# DroneMainBoard.net
KiCad netlist of a schematic drawn in EAGLE
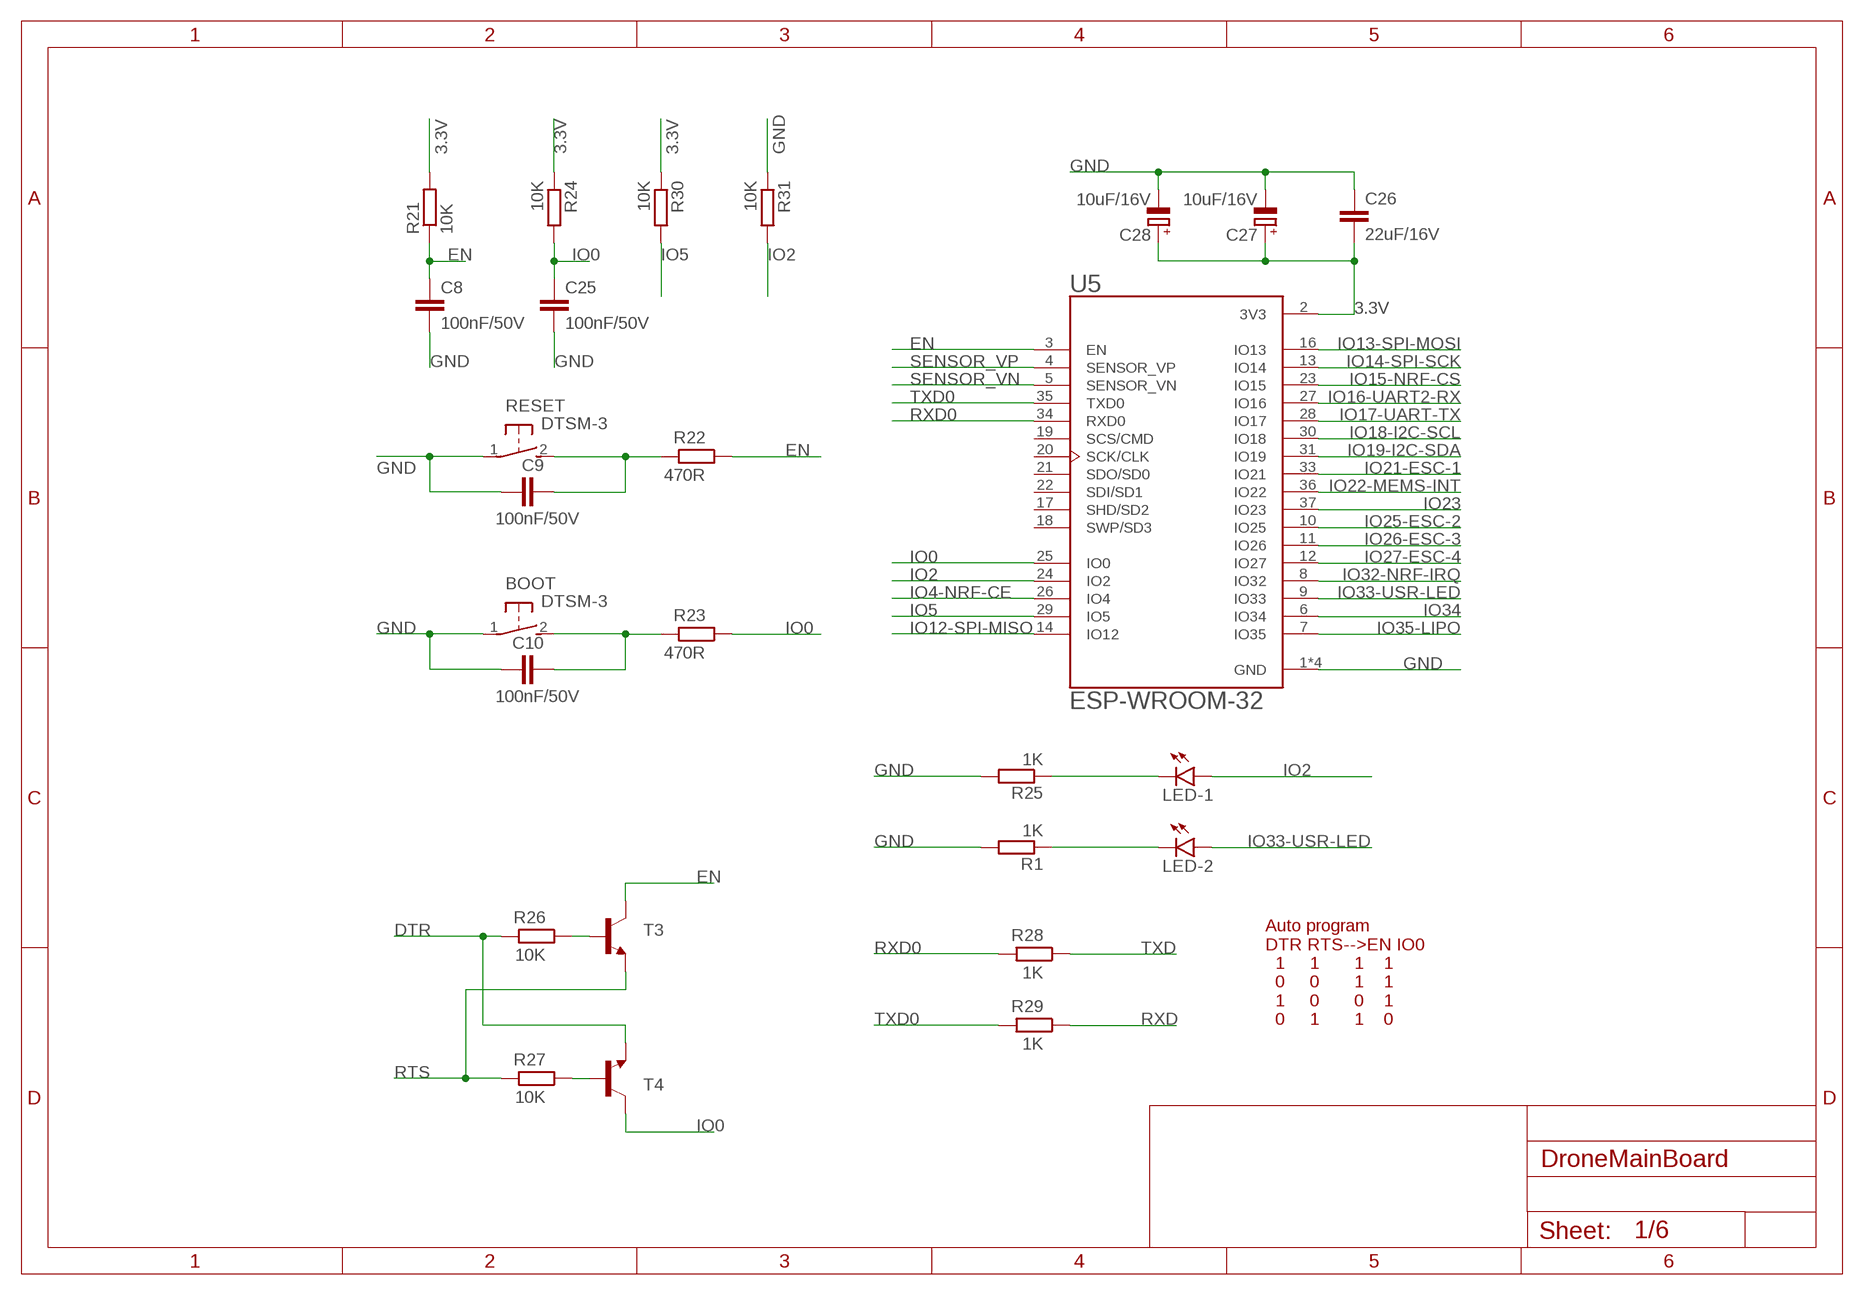
[diagram p0: schematic, sheet 1]
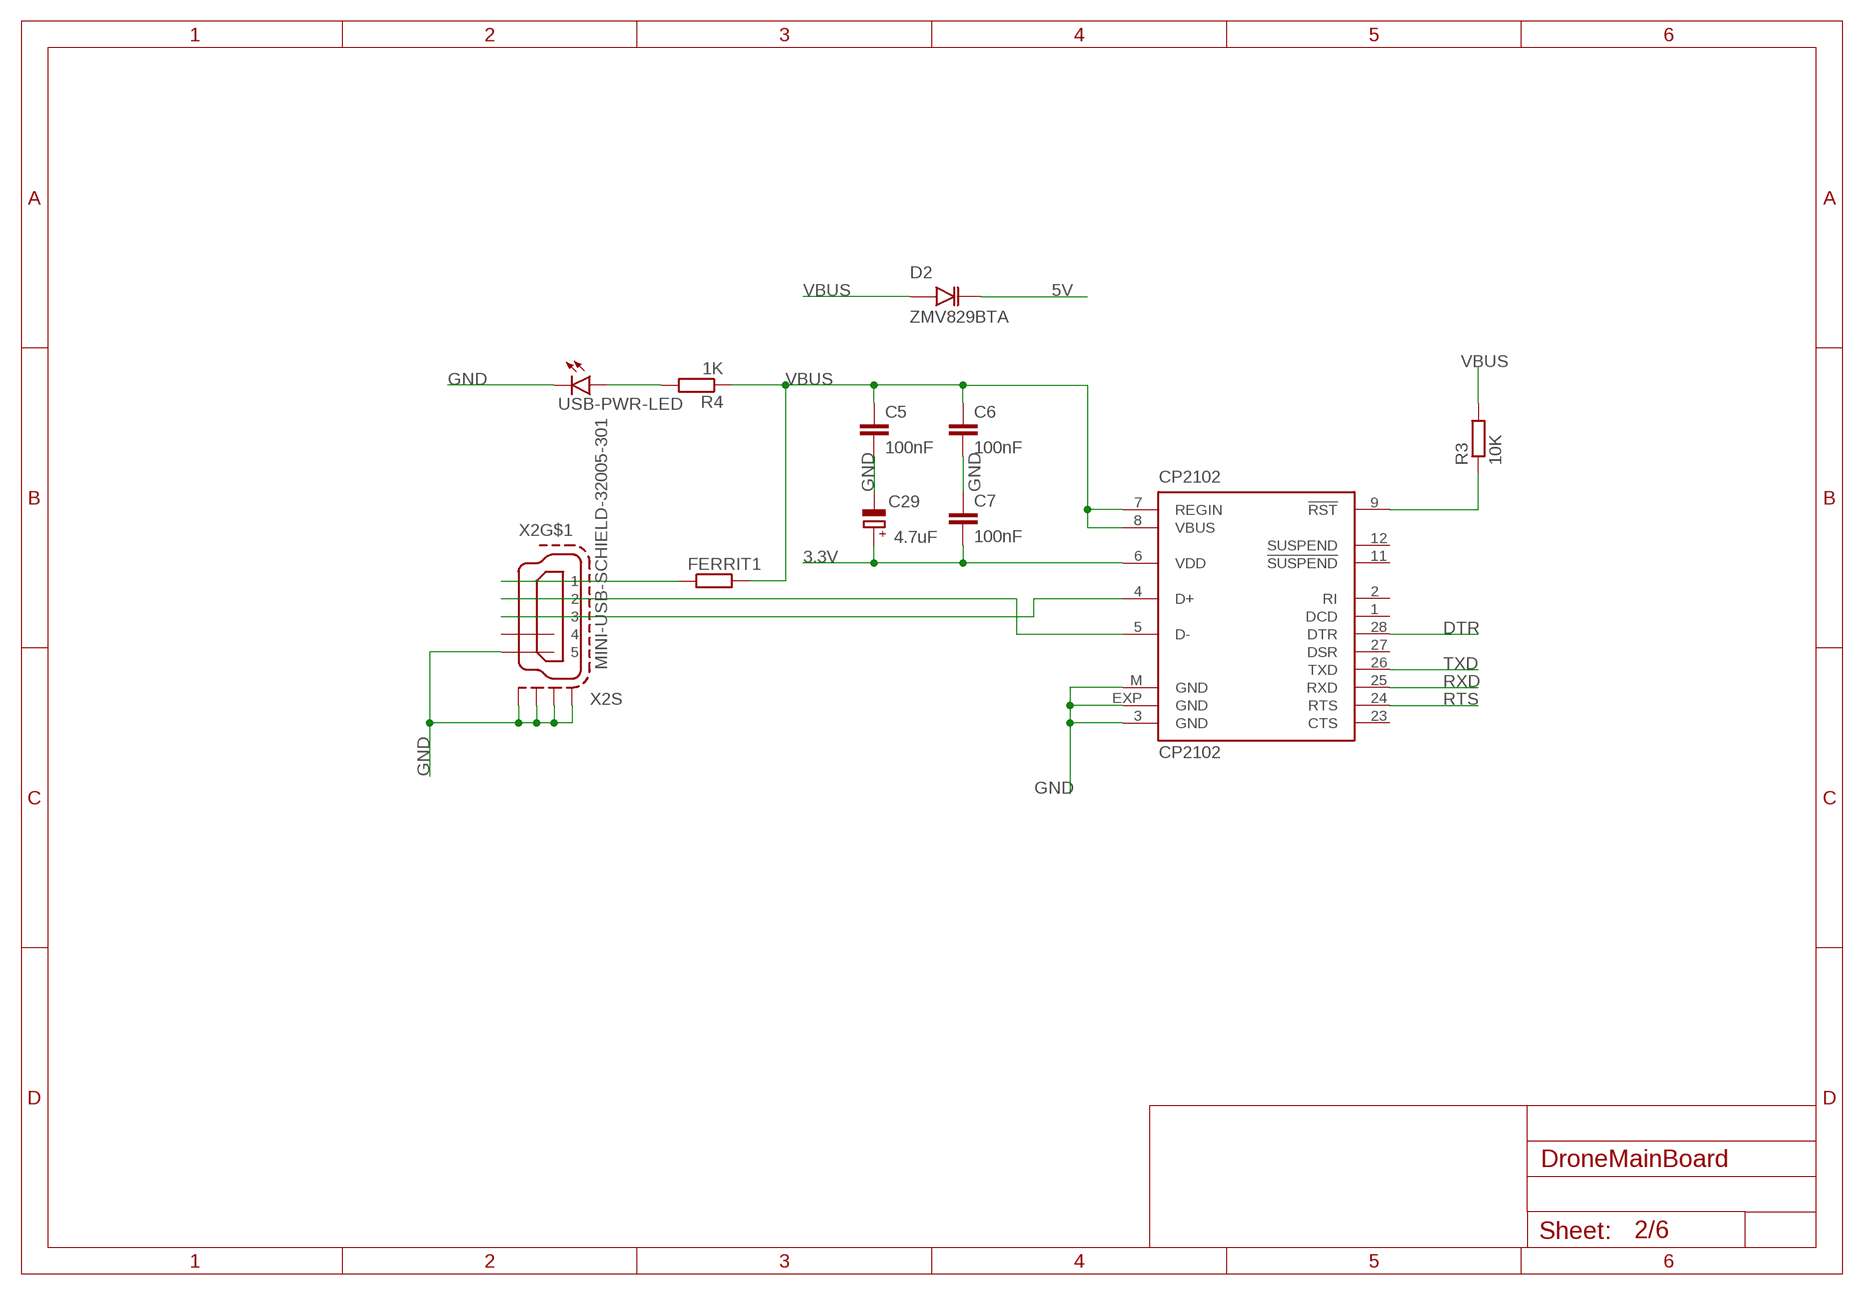
[diagram p1: schematic, sheet 2]
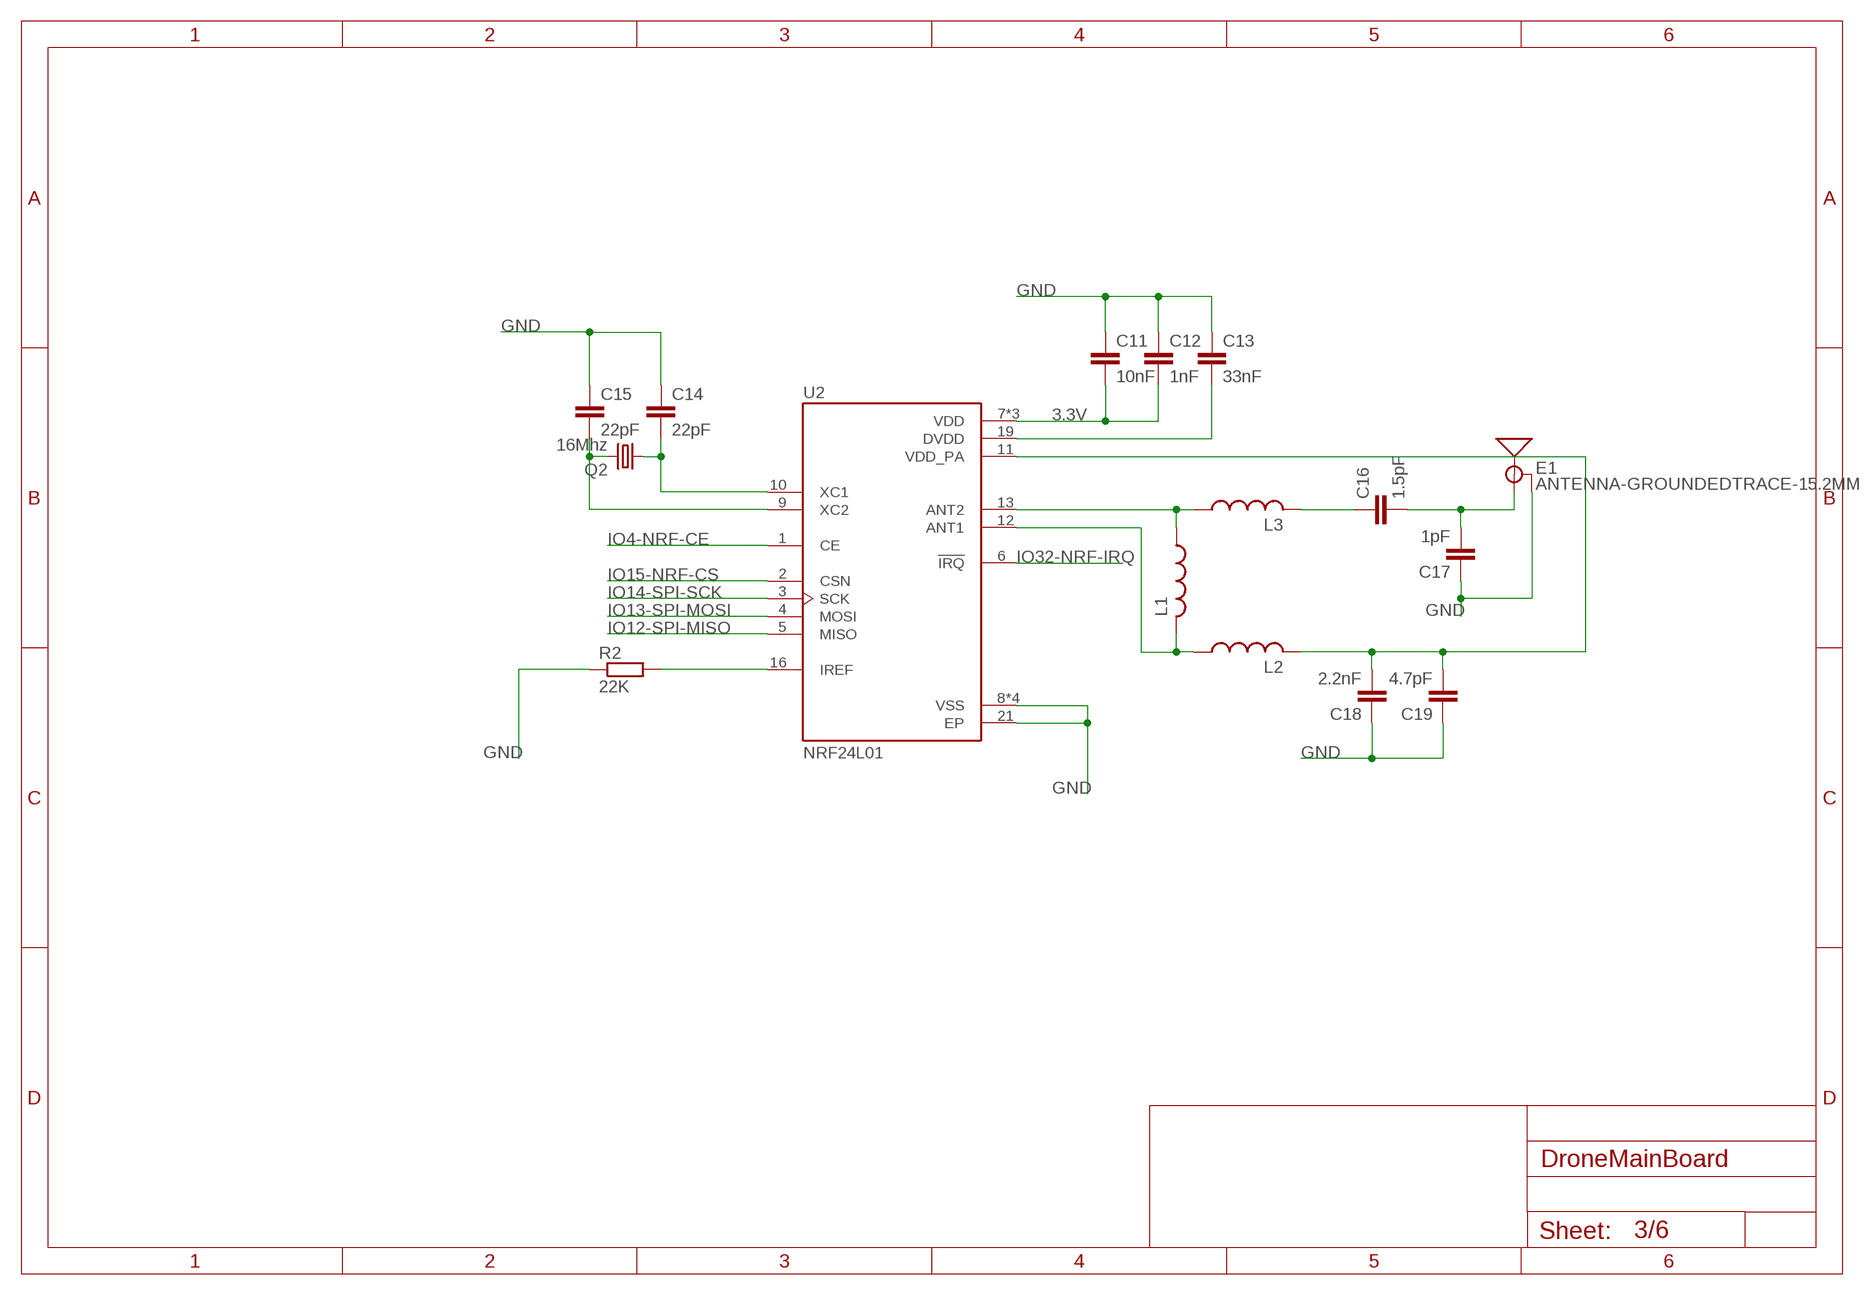
[diagram p2: schematic, sheet 3]
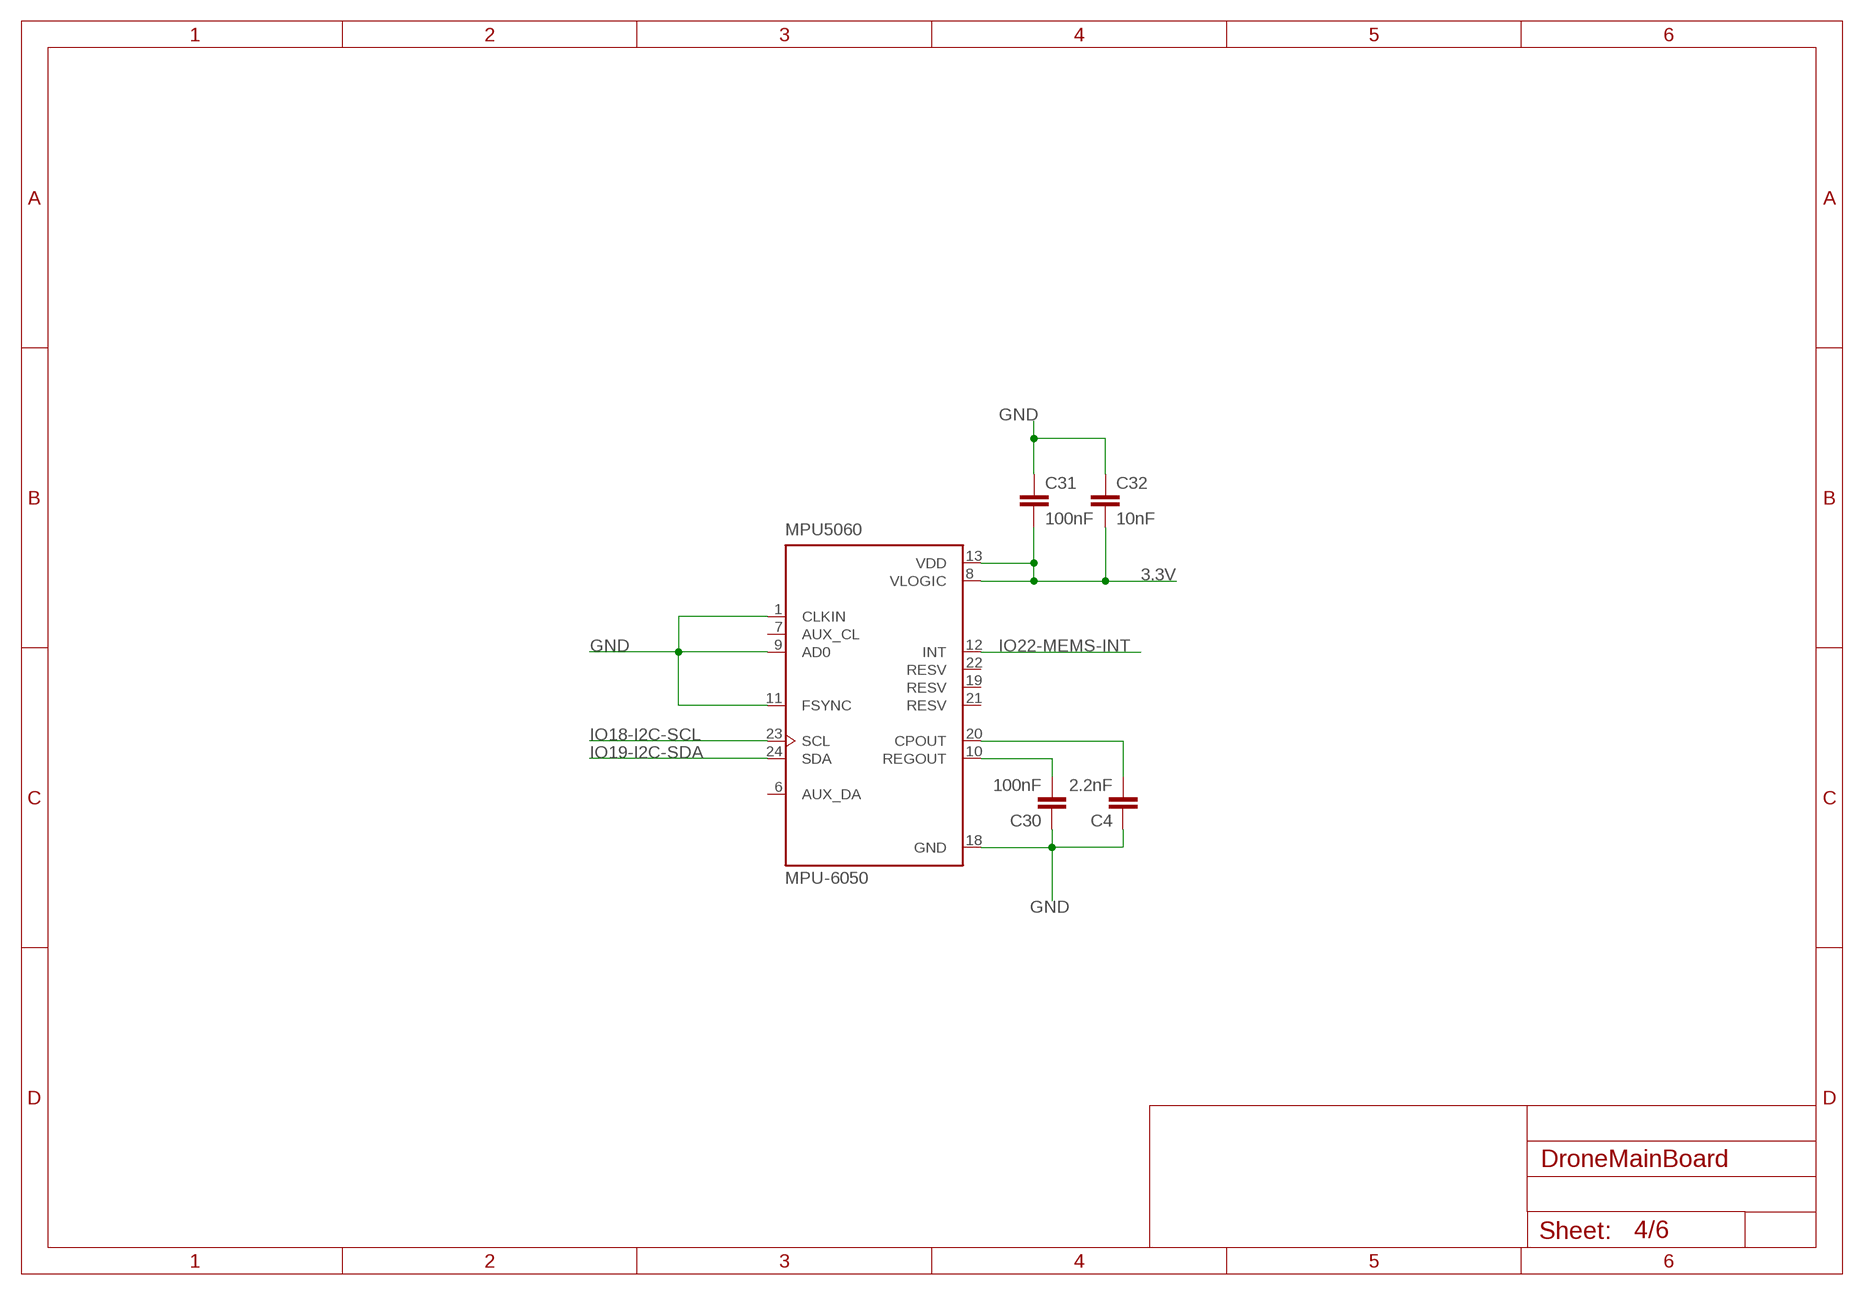
[diagram p3: schematic, sheet 4]
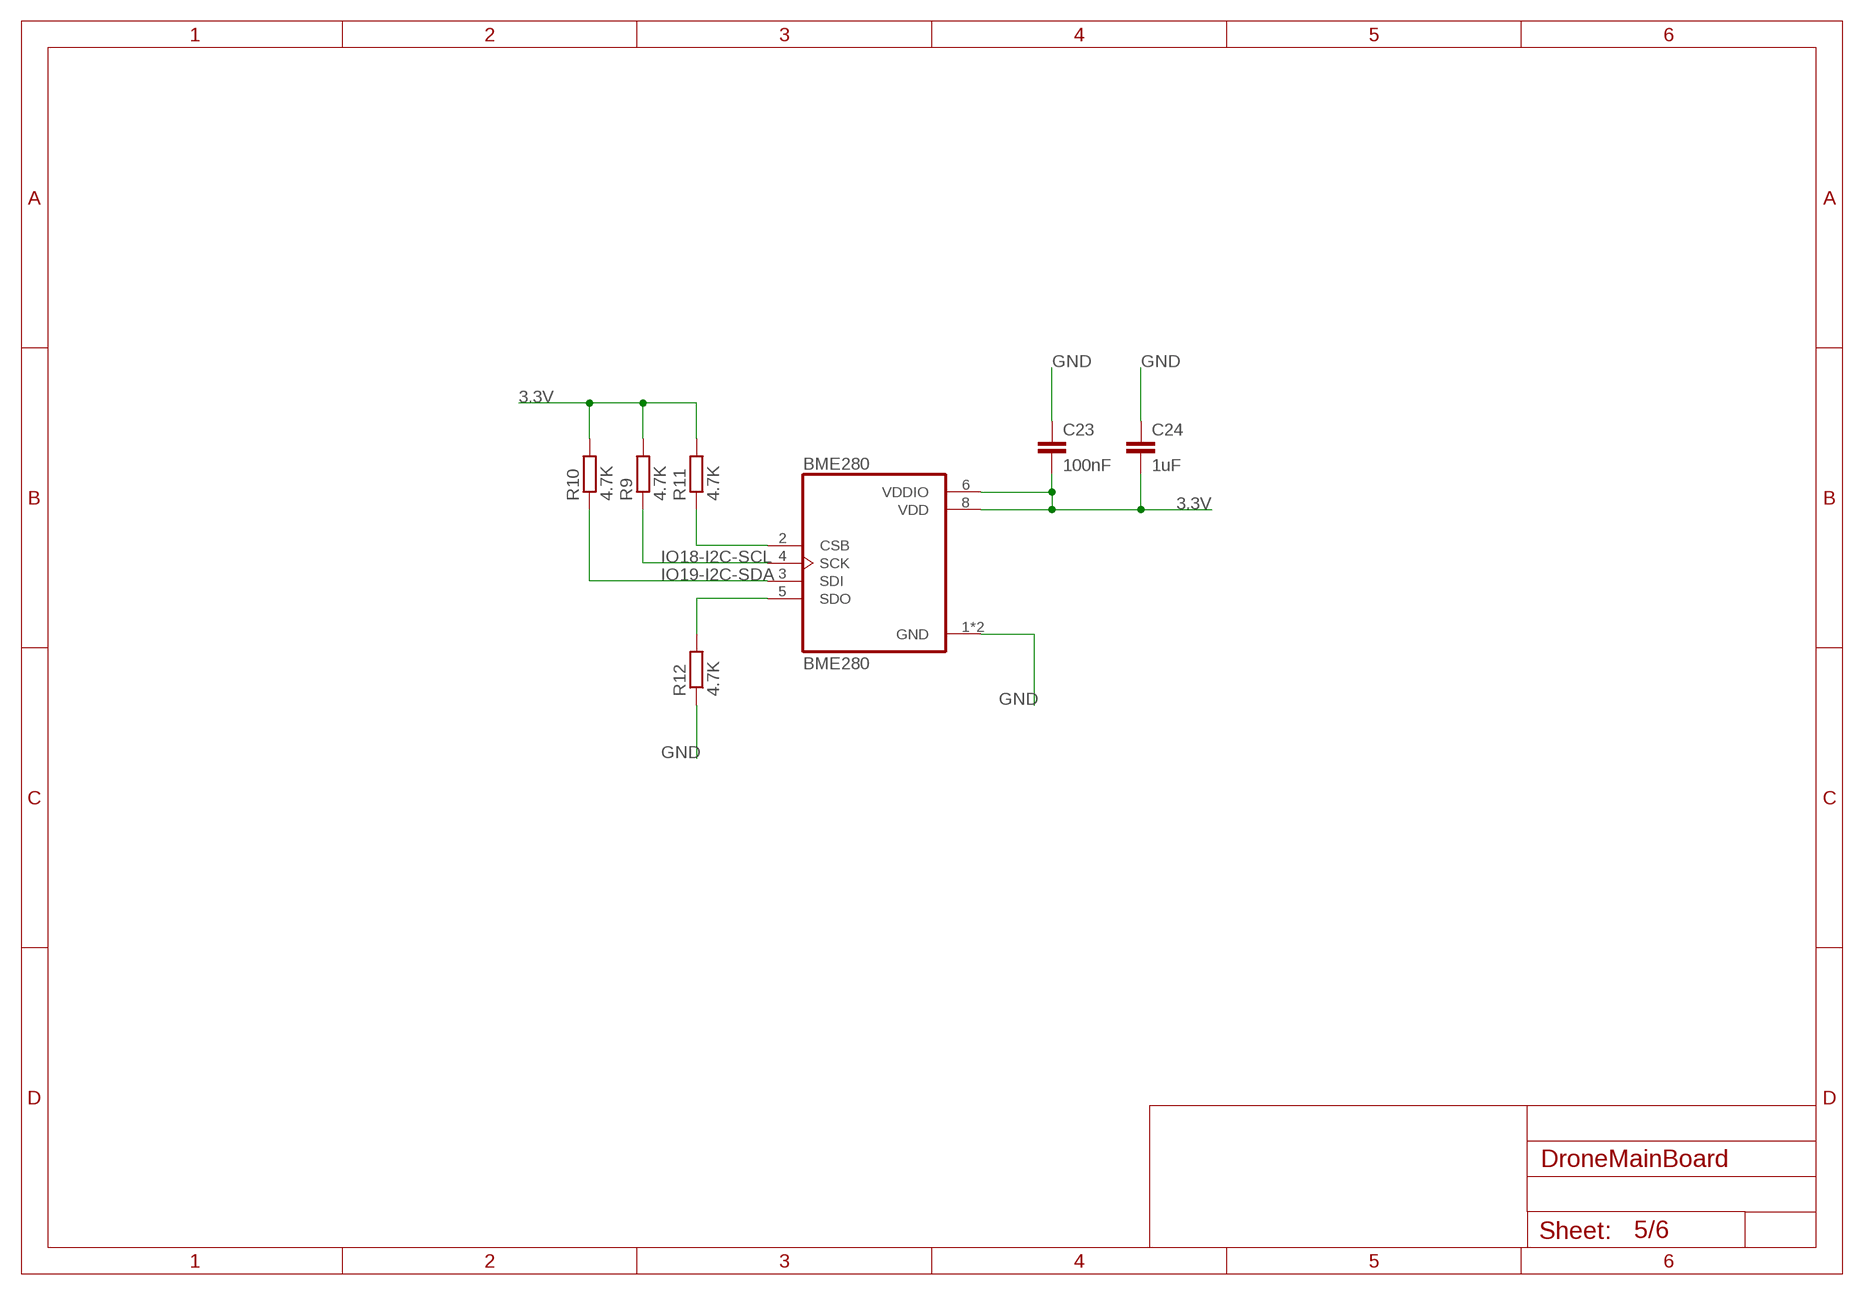
[diagram p4: schematic, sheet 5]
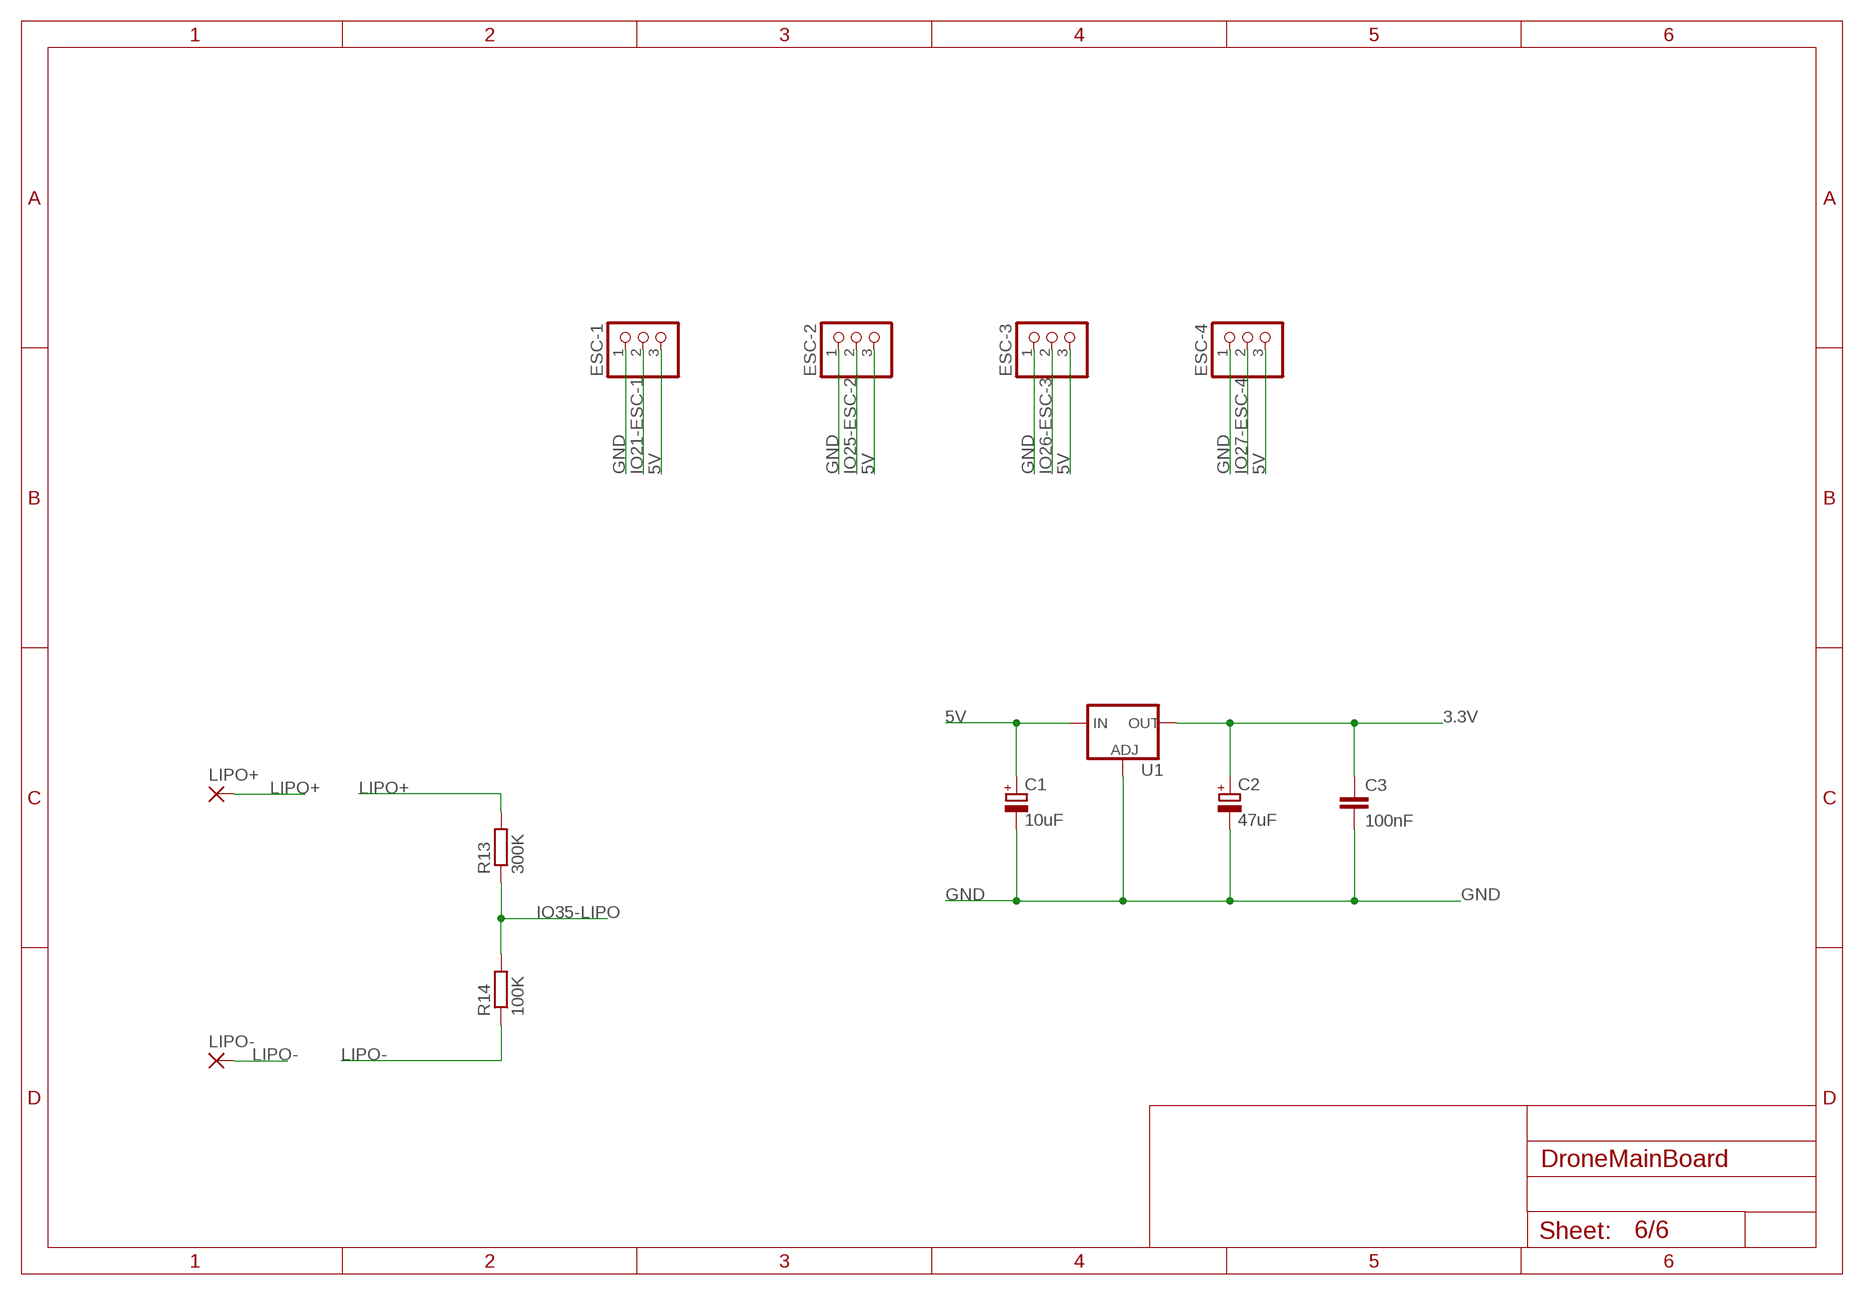
[diagram p5: schematic, sheet 6]

(export (version "E")
  (design (tool "Eeschema 10.0.6"))
  (components
    (comp (ref "C4")
      (value "2.2nF")
      (footprint "eagle-import:C0805")
      (libsource (lib "eagle-import") (part "C-EUC0805"))
    )
    (comp (ref "C30")
      (value "100nF")
      (footprint "eagle-import:C0805")
      (libsource (lib "eagle-import") (part "C-EUC0805"))
    )
    (comp (ref "C31")
      (value "100nF")
      (footprint "eagle-import:C0805")
      (libsource (lib "eagle-import") (part "C-EUC0805"))
    )
    (comp (ref "C32")
      (value "10nF")
      (footprint "eagle-import:C0805")
      (libsource (lib "eagle-import") (part "C-EUC0805"))
    )
    (comp (ref "MPU5060")
      (value "MPU-6050")
      (footprint "eagle-import:QFN50P400X400X95-24N")
      (fields (field (name "MF") "TDK InvenSense"))
      (libsource (lib "eagle-import") (part "MPU-6050"))
    )
    (comp (ref "C5")
      (value "100nF")
      (footprint "eagle-import:C0805")
      (libsource (lib "eagle-import") (part "C-EUC0805"))
    )
    (comp (ref "C6")
      (value "100nF")
      (footprint "eagle-import:C0805")
      (libsource (lib "eagle-import") (part "C-EUC0805"))
    )
    (comp (ref "C7")
      (value "100nF")
      (footprint "eagle-import:C0805")
      (libsource (lib "eagle-import") (part "C-EUC0805"))
    )
    (comp (ref "C29")
      (value "4.7uF")
      (footprint "eagle-import:SMC_A")
      (libsource (lib "eagle-import") (part "CPOL-EUSMCA"))
    )
    (comp (ref "CP2102")
      (value "CP2102")
      (footprint "eagle-import:MLP28")
      (fields (field (name "MF") "FARNELL") (field (name "MPN") "CP2102-GM"))
      (libsource (lib "eagle-import") (part "CP2102"))
    )
    (comp (ref "D2")
      (value "ZMV829BTA")
      (footprint "eagle-import:SOD2512X116N")
      (fields (field (name "MF") "Diodes Inc."))
      (libsource (lib "eagle-import") (part "ZMV829BTA"))
    )
    (comp (ref "FERRIT1")
      (value "R-EU_R0805")
      (footprint "eagle-import:R0805")
      (libsource (lib "eagle-import") (part "R-EU_R0805"))
    )
    (comp (ref "R3")
      (value "10K")
      (footprint "eagle-import:R0805")
      (libsource (lib "eagle-import") (part "R-EU_R0805"))
    )
    (comp (ref "R4")
      (value "1K")
      (footprint "eagle-import:R0805")
      (libsource (lib "eagle-import") (part "R-EU_R0805"))
    )
    (comp (ref "USB-PWR-LED")
      (value "LEDCHIPLED_0805")
      (footprint "eagle-import:CHIPLED_0805")
      (libsource (lib "eagle-import") (part "LEDCHIPLED_0805"))
    )
    (comp (ref "X2")
      (value "MINI-USB-SCHIELD-32005-301")
      (footprint "eagle-import:32005-301")
      (libsource (lib "eagle-import") (part "MINI-USB-SCHIELD-32005-301"))
    )
    (comp (ref "C1")
      (value "10uF")
      (footprint "eagle-import:SMC_A")
      (libsource (lib "eagle-import") (part "CPOL-EUSMCA"))
    )
    (comp (ref "C2")
      (value "47uF")
      (footprint "eagle-import:SMC_A")
      (libsource (lib "eagle-import") (part "CPOL-EUSMCA"))
    )
    (comp (ref "C3")
      (value "100nF")
      (footprint "eagle-import:C0805")
      (libsource (lib "eagle-import") (part "C-EUC0805"))
    )
    (comp (ref "ESC-1")
      (value "PINHD-1X3")
      (footprint "eagle-import:1X03")
      (libsource (lib "eagle-import") (part "PINHD-1X3"))
    )
    (comp (ref "ESC-2")
      (value "PINHD-1X3")
      (footprint "eagle-import:1X03")
      (libsource (lib "eagle-import") (part "PINHD-1X3"))
    )
    (comp (ref "ESC-3")
      (value "PINHD-1X3")
      (footprint "eagle-import:1X03")
      (libsource (lib "eagle-import") (part "PINHD-1X3"))
    )
    (comp (ref "ESC-4")
      (value "PINHD-1X3")
      (footprint "eagle-import:1X03")
      (libsource (lib "eagle-import") (part "PINHD-1X3"))
    )
    (comp (ref "LIPO+")
      (value "2,15/1,0")
      (footprint "eagle-import:2,15_1,0")
      (libsource (lib "eagle-import") (part "2,15/1,0"))
    )
    (comp (ref "LIPO-")
      (value "2,15/1,0")
      (footprint "eagle-import:2,15_1,0")
      (libsource (lib "eagle-import") (part "2,15/1,0"))
    )
    (comp (ref "R13")
      (value "300K")
      (footprint "eagle-import:R0805")
      (libsource (lib "eagle-import") (part "R-EU_R0805"))
    )
    (comp (ref "R14")
      (value "100K")
      (footprint "eagle-import:R0805")
      (libsource (lib "eagle-import") (part "R-EU_R0805"))
    )
    (comp (ref "U1")
      (value "V_REG_LM1117SOT223")
      (footprint "eagle-import:SOT223")
      (libsource (lib "eagle-import") (part "V_REG_LM1117SOT223"))
    )
    (comp (ref "BOOT")
      (value "DTSM-3")
      (footprint "eagle-import:DTSM-3")
      (libsource (lib "eagle-import") (part "DTSM-3"))
    )
    (comp (ref "C8")
      (value "100nF/50V")
      (footprint "eagle-import:C0805")
      (libsource (lib "eagle-import") (part "C-EUC0805"))
    )
    (comp (ref "C9")
      (value "100nF/50V")
      (footprint "eagle-import:C0805")
      (libsource (lib "eagle-import") (part "C-EUC0805"))
    )
    (comp (ref "C10")
      (value "100nF/50V")
      (footprint "eagle-import:C0805")
      (libsource (lib "eagle-import") (part "C-EUC0805"))
    )
    (comp (ref "C25")
      (value "100nF/50V")
      (footprint "eagle-import:C0805")
      (libsource (lib "eagle-import") (part "C-EUC0805"))
    )
    (comp (ref "C26")
      (value "22uF/16V")
      (footprint "eagle-import:C0805")
      (libsource (lib "eagle-import") (part "C-EUC0805"))
    )
    (comp (ref "C27")
      (value "10uF/16V")
      (footprint "eagle-import:SMC_A")
      (libsource (lib "eagle-import") (part "CPOL-EUSMCA"))
    )
    (comp (ref "C28")
      (value "10uF/16V")
      (footprint "eagle-import:SMC_A")
      (libsource (lib "eagle-import") (part "CPOL-EUSMCA"))
    )
    (comp (ref "LED-1")
      (value "LEDCHIP-LED0805")
      (footprint "eagle-import:CHIP-LED0805")
      (libsource (lib "eagle-import") (part "LEDCHIP-LED0805"))
    )
    (comp (ref "LED-2")
      (value "LEDCHIP-LED0805")
      (footprint "eagle-import:CHIP-LED0805")
      (libsource (lib "eagle-import") (part "LEDCHIP-LED0805"))
    )
    (comp (ref "R1")
      (value "1K")
      (footprint "eagle-import:R0805")
      (libsource (lib "eagle-import") (part "R-EU_R0805"))
    )
    (comp (ref "R21")
      (value "10K")
      (footprint "eagle-import:R0805")
      (libsource (lib "eagle-import") (part "R-EU_R0805"))
    )
    (comp (ref "R22")
      (value "470R")
      (footprint "eagle-import:R0805")
      (libsource (lib "eagle-import") (part "R-EU_R0805"))
    )
    (comp (ref "R23")
      (value "470R")
      (footprint "eagle-import:R0805")
      (libsource (lib "eagle-import") (part "R-EU_R0805"))
    )
    (comp (ref "R24")
      (value "10K")
      (footprint "eagle-import:R0805")
      (libsource (lib "eagle-import") (part "R-EU_R0805"))
    )
    (comp (ref "R25")
      (value "1K")
      (footprint "eagle-import:R0805")
      (libsource (lib "eagle-import") (part "R-EU_R0805"))
    )
    (comp (ref "R26")
      (value "10K")
      (footprint "eagle-import:R0805")
      (libsource (lib "eagle-import") (part "R-EU_R0805"))
    )
    (comp (ref "R27")
      (value "10K")
      (footprint "eagle-import:R0805")
      (libsource (lib "eagle-import") (part "R-EU_R0805"))
    )
    (comp (ref "R28")
      (value "1K")
      (footprint "eagle-import:R0805")
      (libsource (lib "eagle-import") (part "R-EU_R0805"))
    )
    (comp (ref "R29")
      (value "1K")
      (footprint "eagle-import:R0805")
      (libsource (lib "eagle-import") (part "R-EU_R0805"))
    )
    (comp (ref "R30")
      (value "10K")
      (footprint "eagle-import:R0805")
      (libsource (lib "eagle-import") (part "R-EU_R0805"))
    )
    (comp (ref "R31")
      (value "10K")
      (footprint "eagle-import:R0805")
      (libsource (lib "eagle-import") (part "R-EU_R0805"))
    )
    (comp (ref "RESET")
      (value "DTSM-3")
      (footprint "eagle-import:DTSM-3")
      (libsource (lib "eagle-import") (part "DTSM-3"))
    )
    (comp (ref "T3")
      (value "-NPN-SOT23-EBC")
      (footprint "eagle-import:SOT23-EBC")
      (libsource (lib "eagle-import") (part "-NPN-SOT23-EBC"))
    )
    (comp (ref "T4")
      (value "-NPN-SOT23-EBC")
      (footprint "eagle-import:SOT23-EBC")
      (libsource (lib "eagle-import") (part "-NPN-SOT23-EBC"))
    )
    (comp (ref "U5")
      (value "ESP-WROOM-32")
      (footprint "eagle-import:MODULE_ESP-WROOM-32")
      (fields (field (name "MF") "Olimex LTD"))
      (libsource (lib "eagle-import") (part "ESP-WROOM-32"))
    )
    (comp (ref "C11")
      (value "10nF")
      (footprint "eagle-import:C0805")
      (libsource (lib "eagle-import") (part "C-EUC0805"))
    )
    (comp (ref "C12")
      (value "1nF")
      (footprint "eagle-import:C0805")
      (libsource (lib "eagle-import") (part "C-EUC0805"))
    )
    (comp (ref "C13")
      (value "33nF")
      (footprint "eagle-import:C0805")
      (libsource (lib "eagle-import") (part "C-EUC0805"))
    )
    (comp (ref "C14")
      (value "22pF")
      (footprint "eagle-import:C0805")
      (libsource (lib "eagle-import") (part "C-EUC0805"))
    )
    (comp (ref "C15")
      (value "22pF")
      (footprint "eagle-import:C0805")
      (libsource (lib "eagle-import") (part "C-EUC0805"))
    )
    (comp (ref "C16")
      (value "1.5pF")
      (footprint "eagle-import:C0805")
      (libsource (lib "eagle-import") (part "C-EUC0805"))
    )
    (comp (ref "C17")
      (value "1pF")
      (footprint "eagle-import:C0805")
      (libsource (lib "eagle-import") (part "C-EUC0805"))
    )
    (comp (ref "C18")
      (value "2.2nF")
      (footprint "eagle-import:C0805")
      (libsource (lib "eagle-import") (part "C-EUC0805"))
    )
    (comp (ref "C19")
      (value "4.7pF")
      (footprint "eagle-import:C0805")
      (libsource (lib "eagle-import") (part "C-EUC0805"))
    )
    (comp (ref "E1")
      (value "ANTENNA-GROUNDEDTRACE-15.2MM")
      (footprint "eagle-import:TRACE_ANTENNA_2.4GHZ_15.2MM")
      (libsource (lib "eagle-import") (part "ANTENNA-GROUNDEDTRACE-15.2MM"))
    )
    (comp (ref "L1")
      (value "L-USL2012C")
      (footprint "eagle-import:L2012C")
      (libsource (lib "eagle-import") (part "L-USL2012C"))
    )
    (comp (ref "L2")
      (value "L-USL2012C")
      (footprint "eagle-import:L2012C")
      (libsource (lib "eagle-import") (part "L-USL2012C"))
    )
    (comp (ref "L3")
      (value "L-USL2012C")
      (footprint "eagle-import:L2012C")
      (libsource (lib "eagle-import") (part "L-USL2012C"))
    )
    (comp (ref "Q2")
      (value "16Mhz")
      (footprint "eagle-import:HC49_S")
      (libsource (lib "eagle-import") (part "CRYSTALHC49S"))
    )
    (comp (ref "R2")
      (value "22K")
      (footprint "eagle-import:R0805")
      (libsource (lib "eagle-import") (part "R-EU_R0805"))
    )
    (comp (ref "U2")
      (value "NRF24L01")
      (footprint "eagle-import:QFN50P400X400X95-21N")
      (fields (field (name "MF") "Nordic"))
      (libsource (lib "eagle-import") (part "NRF24L01"))
    )
    (comp (ref "BME280")
      (value "BME280")
      (footprint "eagle-import:PSON65P250X250X100-8N")
      (fields (field (name "MF") "Bosch"))
      (libsource (lib "eagle-import") (part "BME280"))
    )
    (comp (ref "C23")
      (value "100nF")
      (footprint "eagle-import:C0805")
      (libsource (lib "eagle-import") (part "C-EUC0805"))
    )
    (comp (ref "C24")
      (value "1uF")
      (footprint "eagle-import:C0805")
      (libsource (lib "eagle-import") (part "C-EUC0805"))
    )
    (comp (ref "R9")
      (value "4.7K")
      (footprint "eagle-import:R0805")
      (libsource (lib "eagle-import") (part "R-EU_R0805"))
    )
    (comp (ref "R10")
      (value "4.7K")
      (footprint "eagle-import:R0805")
      (libsource (lib "eagle-import") (part "R-EU_R0805"))
    )
    (comp (ref "R11")
      (value "4.7K")
      (footprint "eagle-import:R0805")
      (libsource (lib "eagle-import") (part "R-EU_R0805"))
    )
    (comp (ref "R12")
      (value "4.7K")
      (footprint "eagle-import:R0805")
      (libsource (lib "eagle-import") (part "R-EU_R0805"))
    )
  )
  (nets
    (net (code "1") (name "3.3V") (class "Default")
      (node (ref "BME280") (pin "6") (pinfunction "VDDIO_6") (pintype "power_in"))
      (node (ref "BME280") (pin "8") (pinfunction "VDD_8") (pintype "power_in"))
      (node (ref "C11") (pin "2") (pinfunction "2_2") (pintype "passive"))
      (node (ref "C12") (pin "2") (pinfunction "2_2") (pintype "passive"))
      (node (ref "C2") (pin "+") (pinfunction "+_+") (pintype "passive"))
      (node (ref "C23") (pin "2") (pinfunction "2_2") (pintype "passive"))
      (node (ref "C24") (pin "2") (pinfunction "2_2") (pintype "passive"))
      (node (ref "C26") (pin "2") (pinfunction "2_2") (pintype "passive"))
      (node (ref "C27") (pin "+") (pinfunction "+_+") (pintype "passive"))
      (node (ref "C28") (pin "+") (pinfunction "+_+") (pintype "passive"))
      (node (ref "C29") (pin "+") (pinfunction "+_+") (pintype "passive"))
      (node (ref "C3") (pin "1") (pinfunction "1_1") (pintype "passive"))
      (node (ref "C31") (pin "2") (pinfunction "2_2") (pintype "passive"))
      (node (ref "C32") (pin "2") (pinfunction "2_2") (pintype "passive"))
      (node (ref "C7") (pin "2") (pinfunction "2_2") (pintype "passive"))
      (node (ref "CP2102") (pin "6") (pinfunction "VDD_6") (pintype "power_in"))
      (node (ref "MPU5060") (pin "13") (pinfunction "VDD_13") (pintype "power_in"))
      (node (ref "MPU5060") (pin "8") (pinfunction "VLOGIC_8") (pintype "power_in"))
      (node (ref "R10") (pin "2") (pinfunction "2_2") (pintype "passive"))
      (node (ref "R11") (pin "2") (pinfunction "2_2") (pintype "passive"))
      (node (ref "R21") (pin "2") (pinfunction "2_2") (pintype "passive"))
      (node (ref "R24") (pin "1") (pinfunction "1_1") (pintype "passive"))
      (node (ref "R30") (pin "1") (pinfunction "1_1") (pintype "passive"))
      (node (ref "R9") (pin "2") (pinfunction "2_2") (pintype "passive"))
      (node (ref "U1") (pin "2") (pinfunction "OUT_2") (pintype "output"))
      (node (ref "U1") (pin "4") (pinfunction "OUT_4") (pintype "output"))
      (node (ref "U2") (pin "15") (pinfunction "VDD_15") (pintype "power_in"))
      (node (ref "U2") (pin "18") (pinfunction "VDD_18") (pintype "power_in"))
      (node (ref "U2") (pin "7") (pinfunction "VDD_7") (pintype "power_in"))
      (node (ref "U5") (pin "2") (pinfunction "3V3_2") (pintype "power_in"))
    )
    (net (code "2") (name "5V") (class "Default")
      (node (ref "C1") (pin "+") (pinfunction "+_+") (pintype "passive"))
      (node (ref "D2") (pin "K") (pinfunction "K_K") (pintype "passive"))
      (node (ref "ESC-1") (pin "3") (pinfunction "3_3") (pintype "passive"))
      (node (ref "ESC-2") (pin "3") (pinfunction "3_3") (pintype "passive"))
      (node (ref "ESC-3") (pin "3") (pinfunction "3_3") (pintype "passive"))
      (node (ref "ESC-4") (pin "3") (pinfunction "3_3") (pintype "passive"))
      (node (ref "U1") (pin "3") (pinfunction "IN_3") (pintype "input"))
    )
    (net (code "3") (name "DTR") (class "Default")
      (node (ref "CP2102") (pin "28") (pinfunction "DTR_28") (pintype "output"))
      (node (ref "R26") (pin "2") (pinfunction "2_2") (pintype "passive"))
      (node (ref "T4") (pin "E") (pinfunction "E_E") (pintype "passive"))
    )
    (net (code "4") (name "EN") (class "Default")
      (node (ref "C8") (pin "1") (pinfunction "1_1") (pintype "passive"))
      (node (ref "R21") (pin "1") (pinfunction "1_1") (pintype "passive"))
      (node (ref "R22") (pin "1") (pinfunction "1_1") (pintype "passive"))
      (node (ref "T3") (pin "C") (pinfunction "C_C") (pintype "passive"))
      (node (ref "U5") (pin "3") (pinfunction "EN_3") (pintype "input"))
    )
    (net (code "5") (name "GND") (class "Default")
      (node (ref "BME280") (pin "1") (pinfunction "GND_1") (pintype "power_in"))
      (node (ref "BME280") (pin "7") (pinfunction "GND_7") (pintype "power_in"))
      (node (ref "BOOT") (pin "1") (pinfunction "1_1") (pintype "passive"))
      (node (ref "C1") (pin "-") (pinfunction "-_-") (pintype "passive"))
      (node (ref "C10") (pin "1") (pinfunction "1_1") (pintype "passive"))
      (node (ref "C11") (pin "1") (pinfunction "1_1") (pintype "passive"))
      (node (ref "C12") (pin "1") (pinfunction "1_1") (pintype "passive"))
      (node (ref "C13") (pin "1") (pinfunction "1_1") (pintype "passive"))
      (node (ref "C14") (pin "1") (pinfunction "1_1") (pintype "passive"))
      (node (ref "C15") (pin "1") (pinfunction "1_1") (pintype "passive"))
      (node (ref "C17") (pin "1") (pinfunction "1_1") (pintype "passive"))
      (node (ref "C18") (pin "1") (pinfunction "1_1") (pintype "passive"))
      (node (ref "C19") (pin "1") (pinfunction "1_1") (pintype "passive"))
      (node (ref "C2") (pin "-") (pinfunction "-_-") (pintype "passive"))
      (node (ref "C23") (pin "1") (pinfunction "1_1") (pintype "passive"))
      (node (ref "C24") (pin "1") (pinfunction "1_1") (pintype "passive"))
      (node (ref "C25") (pin "2") (pinfunction "2_2") (pintype "passive"))
      (node (ref "C26") (pin "1") (pinfunction "1_1") (pintype "passive"))
      (node (ref "C27") (pin "-") (pinfunction "-_-") (pintype "passive"))
      (node (ref "C28") (pin "-") (pinfunction "-_-") (pintype "passive"))
      (node (ref "C29") (pin "-") (pinfunction "-_-") (pintype "passive"))
      (node (ref "C3") (pin "2") (pinfunction "2_2") (pintype "passive"))
      (node (ref "C30") (pin "1") (pinfunction "1_1") (pintype "passive"))
      (node (ref "C31") (pin "1") (pinfunction "1_1") (pintype "passive"))
      (node (ref "C32") (pin "1") (pinfunction "1_1") (pintype "passive"))
      (node (ref "C4") (pin "1") (pinfunction "1_1") (pintype "passive"))
      (node (ref "C5") (pin "2") (pinfunction "2_2") (pintype "passive"))
      (node (ref "C6") (pin "2") (pinfunction "2_2") (pintype "passive"))
      (node (ref "C7") (pin "1") (pinfunction "1_1") (pintype "passive"))
      (node (ref "C8") (pin "2") (pinfunction "2_2") (pintype "passive"))
      (node (ref "C9") (pin "1") (pinfunction "1_1") (pintype "passive"))
      (node (ref "CP2102") (pin "3") (pinfunction "GND_3") (pintype "power_in"))
      (node (ref "CP2102") (pin "EXP") (pinfunction "GND_EXP") (pintype "power_in"))
      (node (ref "CP2102") (pin "M") (pinfunction "GND_M") (pintype "power_in"))
      (node (ref "E1") (pin "GND") (pinfunction "GND_GND") (pintype "bidirectional"))
      (node (ref "ESC-1") (pin "1") (pinfunction "1_1") (pintype "passive"))
      (node (ref "ESC-2") (pin "1") (pinfunction "1_1") (pintype "passive"))
      (node (ref "ESC-3") (pin "1") (pinfunction "1_1") (pintype "passive"))
      (node (ref "ESC-4") (pin "1") (pinfunction "1_1") (pintype "passive"))
      (node (ref "MPU5060") (pin "1") (pinfunction "CLKIN_1") (pintype "input"))
      (node (ref "MPU5060") (pin "11") (pinfunction "FSYNC_11") (pintype "input"))
      (node (ref "MPU5060") (pin "18") (pinfunction "GND_18") (pintype "power_in"))
      (node (ref "MPU5060") (pin "9") (pinfunction "AD0_9") (pintype "input"))
      (node (ref "R1") (pin "2") (pinfunction "2_2") (pintype "passive"))
      (node (ref "R12") (pin "1") (pinfunction "1_1") (pintype "passive"))
      (node (ref "R2") (pin "1") (pinfunction "1_1") (pintype "passive"))
      (node (ref "R25") (pin "2") (pinfunction "2_2") (pintype "passive"))
      (node (ref "R31") (pin "1") (pinfunction "1_1") (pintype "passive"))
      (node (ref "RESET") (pin "1") (pinfunction "1_1") (pintype "passive"))
      (node (ref "U1") (pin "1") (pinfunction "ADJ_1") (pintype "input"))
      (node (ref "U2") (pin "14") (pinfunction "VSS_14") (pintype "power_in"))
      (node (ref "U2") (pin "17") (pinfunction "VSS_17") (pintype "power_in"))
      (node (ref "U2") (pin "20") (pinfunction "VSS_20") (pintype "power_in"))
      (node (ref "U2") (pin "21") (pinfunction "EP_21") (pintype "power_in"))
      (node (ref "U2") (pin "8") (pinfunction "VSS_8") (pintype "power_in"))
      (node (ref "U5") (pin "1") (pinfunction "GND_1") (pintype "power_in"))
      (node (ref "U5") (pin "1.1") (pinfunction "GND_1.1") (pintype "power_in"))
      (node (ref "U5") (pin "15") (pinfunction "GND_15") (pintype "power_in"))
      (node (ref "U5") (pin "38") (pinfunction "GND_38") (pintype "power_in"))
      (node (ref "USB-PWR-LED") (pin "C") (pinfunction "C_C") (pintype "passive"))
      (node (ref "X2") (pin "5") (pinfunction "5_5") (pintype "passive"))
      (node (ref "X2") (pin "M1") (pinfunction "S1_M1") (pintype "passive"))
      (node (ref "X2") (pin "M2") (pinfunction "S2_M2") (pintype "passive"))
      (node (ref "X2") (pin "M3") (pinfunction "S3_M3") (pintype "passive"))
      (node (ref "X2") (pin "M4") (pinfunction "S4_M4") (pintype "passive"))
    )
    (net (code "6") (name "IO0") (class "Default")
      (node (ref "C25") (pin "1") (pinfunction "1_1") (pintype "passive"))
      (node (ref "R23") (pin "1") (pinfunction "1_1") (pintype "passive"))
      (node (ref "R24") (pin "2") (pinfunction "2_2") (pintype "passive"))
      (node (ref "T4") (pin "C") (pinfunction "C_C") (pintype "passive"))
      (node (ref "U5") (pin "25") (pinfunction "IO0_25") (pintype "bidirectional"))
    )
    (net (code "7") (name "IO2") (class "Default")
      (node (ref "LED-1") (pin "A") (pinfunction "A_A") (pintype "passive"))
      (node (ref "R31") (pin "2") (pinfunction "2_2") (pintype "passive"))
      (node (ref "U5") (pin "24") (pinfunction "IO2_24") (pintype "bidirectional"))
    )
    (net (code "8") (name "IO4-NRF-CE") (class "Default")
      (node (ref "U2") (pin "1") (pinfunction "CE_1") (pintype "input"))
      (node (ref "U5") (pin "26") (pinfunction "IO4_26") (pintype "bidirectional"))
    )
    (net (code "9") (name "IO5") (class "Default")
      (node (ref "R30") (pin "2") (pinfunction "2_2") (pintype "passive"))
      (node (ref "U5") (pin "29") (pinfunction "IO5_29") (pintype "bidirectional"))
    )
    (net (code "10") (name "IO12-SPI-MISO") (class "Default")
      (node (ref "U2") (pin "5") (pinfunction "MISO_5") (pintype "output"))
      (node (ref "U5") (pin "14") (pinfunction "IO12_14") (pintype "bidirectional"))
    )
    (net (code "11") (name "IO13-SPI-MOSI") (class "Default")
      (node (ref "U2") (pin "4") (pinfunction "MOSI_4") (pintype "input"))
      (node (ref "U5") (pin "16") (pinfunction "IO13_16") (pintype "bidirectional"))
    )
    (net (code "12") (name "IO14-SPI-SCK") (class "Default")
      (node (ref "U2") (pin "3") (pinfunction "SCK_3") (pintype "input"))
      (node (ref "U5") (pin "13") (pinfunction "IO14_13") (pintype "bidirectional"))
    )
    (net (code "13") (name "IO15-NRF-CS") (class "Default")
      (node (ref "U2") (pin "2") (pinfunction "CSN_2") (pintype "input"))
      (node (ref "U5") (pin "23") (pinfunction "IO15_23") (pintype "bidirectional"))
    )
    (net (code "14") (name "IO16-UART2-RX") (class "Default")
      (node (ref "U5") (pin "27") (pinfunction "IO16_27") (pintype "bidirectional"))
    )
    (net (code "15") (name "IO17-UART-TX") (class "Default")
      (node (ref "U5") (pin "28") (pinfunction "IO17_28") (pintype "bidirectional"))
    )
    (net (code "16") (name "IO18-I2C-SCL") (class "Default")
      (node (ref "BME280") (pin "4") (pinfunction "SCK_4") (pintype "input"))
      (node (ref "MPU5060") (pin "23") (pinfunction "SCL_23") (pintype "input"))
      (node (ref "R9") (pin "1") (pinfunction "1_1") (pintype "passive"))
      (node (ref "U5") (pin "30") (pinfunction "IO18_30") (pintype "bidirectional"))
    )
    (net (code "17") (name "IO19-I2C-SDA") (class "Default")
      (node (ref "BME280") (pin "3") (pinfunction "SDI_3") (pintype "bidirectional"))
      (node (ref "MPU5060") (pin "24") (pinfunction "SDA_24") (pintype "bidirectional"))
      (node (ref "R10") (pin "1") (pinfunction "1_1") (pintype "passive"))
      (node (ref "U5") (pin "31") (pinfunction "IO19_31") (pintype "bidirectional"))
    )
    (net (code "18") (name "IO21-ESC-1") (class "Default")
      (node (ref "ESC-1") (pin "2") (pinfunction "2_2") (pintype "passive"))
      (node (ref "U5") (pin "33") (pinfunction "IO21_33") (pintype "bidirectional"))
    )
    (net (code "19") (name "IO22-MEMS-INT") (class "Default")
      (node (ref "MPU5060") (pin "12") (pinfunction "INT_12") (pintype "output"))
      (node (ref "U5") (pin "36") (pinfunction "IO22_36") (pintype "bidirectional"))
    )
    (net (code "20") (name "IO23") (class "Default")
      (node (ref "U5") (pin "37") (pinfunction "IO23_37") (pintype "bidirectional"))
    )
    (net (code "21") (name "IO25-ESC-2") (class "Default")
      (node (ref "ESC-2") (pin "2") (pinfunction "2_2") (pintype "passive"))
      (node (ref "U5") (pin "10") (pinfunction "IO25_10") (pintype "bidirectional"))
    )
    (net (code "22") (name "IO26-ESC-3") (class "Default")
      (node (ref "ESC-3") (pin "2") (pinfunction "2_2") (pintype "passive"))
      (node (ref "U5") (pin "11") (pinfunction "IO26_11") (pintype "bidirectional"))
    )
    (net (code "23") (name "IO27-ESC-4") (class "Default")
      (node (ref "ESC-4") (pin "2") (pinfunction "2_2") (pintype "passive"))
      (node (ref "U5") (pin "12") (pinfunction "IO27_12") (pintype "bidirectional"))
    )
    (net (code "24") (name "IO32-NRF-IRQ") (class "Default")
      (node (ref "U2") (pin "6") (pinfunction "~{IRQ}_6") (pintype "output"))
      (node (ref "U5") (pin "8") (pinfunction "IO32_8") (pintype "bidirectional"))
    )
    (net (code "25") (name "IO33-USR-LED") (class "Default")
      (node (ref "LED-2") (pin "A") (pinfunction "A_A") (pintype "passive"))
      (node (ref "U5") (pin "9") (pinfunction "IO33_9") (pintype "bidirectional"))
    )
    (net (code "26") (name "IO34") (class "Default")
      (node (ref "U5") (pin "6") (pinfunction "IO34_6") (pintype "bidirectional"))
    )
    (net (code "27") (name "IO35-LIPO") (class "Default")
      (node (ref "R13") (pin "1") (pinfunction "1_1") (pintype "passive"))
      (node (ref "R14") (pin "2") (pinfunction "2_2") (pintype "passive"))
      (node (ref "U5") (pin "7") (pinfunction "IO35_7") (pintype "bidirectional"))
    )
    (net (code "28") (name "LIPO+") (class "Default")
      (node (ref "LIPO+") (pin "1") (pinfunction "P_1") (pintype "passive"))
      (node (ref "R13") (pin "2") (pinfunction "2_2") (pintype "passive"))
    )
    (net (code "29") (name "LIPO-") (class "Default")
      (node (ref "LIPO-") (pin "1") (pinfunction "P_1") (pintype "passive"))
      (node (ref "R14") (pin "1") (pinfunction "1_1") (pintype "passive"))
    )
    (net (code "30") (name "Net-(BME280-CSB)") (class "Default")
      (node (ref "BME280") (pin "2") (pinfunction "CSB_2") (pintype "input"))
      (node (ref "R11") (pin "1") (pinfunction "1_1") (pintype "passive"))
    )
    (net (code "31") (name "Net-(BME280-SDO)") (class "Default")
      (node (ref "BME280") (pin "5") (pinfunction "SDO_5") (pintype "bidirectional"))
      (node (ref "R12") (pin "2") (pinfunction "2_2") (pintype "passive"))
    )
    (net (code "32") (name "Net-(BOOT-Pad2)") (class "Default")
      (node (ref "BOOT") (pin "2") (pinfunction "2_2") (pintype "passive"))
      (node (ref "C10") (pin "2") (pinfunction "2_2") (pintype "passive"))
      (node (ref "R23") (pin "2") (pinfunction "2_2") (pintype "passive"))
    )
    (net (code "33") (name "Net-(C9-Pad2)") (class "Default")
      (node (ref "C9") (pin "2") (pinfunction "2_2") (pintype "passive"))
      (node (ref "R22") (pin "2") (pinfunction "2_2") (pintype "passive"))
      (node (ref "RESET") (pin "2") (pinfunction "2_2") (pintype "passive"))
    )
    (net (code "34") (name "Net-(C16-Pad1)") (class "Default")
      (node (ref "C16") (pin "1") (pinfunction "1_1") (pintype "passive"))
      (node (ref "L3") (pin "2") (pinfunction "2_2") (pintype "passive"))
    )
    (net (code "35") (name "Net-(CP2102-D+)") (class "Default")
      (node (ref "CP2102") (pin "4") (pinfunction "D+_4") (pintype "bidirectional"))
      (node (ref "X2") (pin "3") (pinfunction "3_3") (pintype "passive"))
    )
    (net (code "36") (name "Net-(CP2102-D-)") (class "Default")
      (node (ref "CP2102") (pin "5") (pinfunction "D-_5") (pintype "bidirectional"))
      (node (ref "X2") (pin "2") (pinfunction "2_2") (pintype "passive"))
    )
    (net (code "37") (name "Net-(CP2102-~{RST})") (class "Default")
      (node (ref "CP2102") (pin "9") (pinfunction "~{RST}_9") (pintype "bidirectional"))
      (node (ref "R3") (pin "1") (pinfunction "1_1") (pintype "passive"))
    )
    (net (code "38") (name "Net-(E1-SIGNAL)") (class "Default")
      (node (ref "C16") (pin "2") (pinfunction "2_2") (pintype "passive"))
      (node (ref "C17") (pin "2") (pinfunction "2_2") (pintype "passive"))
      (node (ref "E1") (pin "ANT") (pinfunction "SIGNAL_ANT") (pintype "bidirectional"))
    )
    (net (code "39") (name "Net-(FERRIT1-Pad1)") (class "Default")
      (node (ref "FERRIT1") (pin "1") (pinfunction "1_1") (pintype "passive"))
      (node (ref "X2") (pin "1") (pinfunction "1_1") (pintype "passive"))
    )
    (net (code "40") (name "Net-(LED-1-PadC)") (class "Default")
      (node (ref "LED-1") (pin "C") (pinfunction "C_C") (pintype "passive"))
      (node (ref "R25") (pin "1") (pinfunction "1_1") (pintype "passive"))
    )
    (net (code "41") (name "Net-(LED-2-PadC)") (class "Default")
      (node (ref "LED-2") (pin "C") (pinfunction "C_C") (pintype "passive"))
      (node (ref "R1") (pin "1") (pinfunction "1_1") (pintype "passive"))
    )
    (net (code "42") (name "Net-(MPU5060-CPOUT)") (class "Default")
      (node (ref "C4") (pin "2") (pinfunction "2_2") (pintype "passive"))
      (node (ref "MPU5060") (pin "20") (pinfunction "CPOUT_20") (pintype "passive"))
    )
    (net (code "43") (name "Net-(MPU5060-REGOUT)") (class "Default")
      (node (ref "C30") (pin "2") (pinfunction "2_2") (pintype "passive"))
      (node (ref "MPU5060") (pin "10") (pinfunction "REGOUT_10") (pintype "passive"))
    )
    (net (code "44") (name "Net-(R4-Pad2)") (class "Default")
      (node (ref "R4") (pin "2") (pinfunction "2_2") (pintype "passive"))
      (node (ref "USB-PWR-LED") (pin "A") (pinfunction "A_A") (pintype "passive"))
    )
    (net (code "45") (name "Net-(R26-Pad1)") (class "Default")
      (node (ref "R26") (pin "1") (pinfunction "1_1") (pintype "passive"))
      (node (ref "T3") (pin "B") (pinfunction "B_B") (pintype "passive"))
    )
    (net (code "46") (name "Net-(R27-Pad1)") (class "Default")
      (node (ref "R27") (pin "1") (pinfunction "1_1") (pintype "passive"))
      (node (ref "T4") (pin "B") (pinfunction "B_B") (pintype "passive"))
    )
    (net (code "47") (name "Net-(U2-ANT1)") (class "Default")
      (node (ref "L1") (pin "2") (pinfunction "2_2") (pintype "passive"))
      (node (ref "L2") (pin "1") (pinfunction "1_1") (pintype "passive"))
      (node (ref "U2") (pin "12") (pinfunction "ANT1_12") (pintype "bidirectional"))
    )
    (net (code "48") (name "Net-(U2-ANT2)") (class "Default")
      (node (ref "L1") (pin "1") (pinfunction "1_1") (pintype "passive"))
      (node (ref "L3") (pin "1") (pinfunction "1_1") (pintype "passive"))
      (node (ref "U2") (pin "13") (pinfunction "ANT2_13") (pintype "bidirectional"))
    )
    (net (code "49") (name "Net-(U2-DVDD)") (class "Default")
      (node (ref "C13") (pin "2") (pinfunction "2_2") (pintype "passive"))
      (node (ref "U2") (pin "19") (pinfunction "DVDD_19") (pintype "power_in"))
    )
    (net (code "50") (name "Net-(U2-IREF)") (class "Default")
      (node (ref "R2") (pin "2") (pinfunction "2_2") (pintype "passive"))
      (node (ref "U2") (pin "16") (pinfunction "IREF_16") (pintype "input"))
    )
    (net (code "51") (name "Net-(U2-VDD_PA)") (class "Default")
      (node (ref "C18") (pin "2") (pinfunction "2_2") (pintype "passive"))
      (node (ref "C19") (pin "2") (pinfunction "2_2") (pintype "passive"))
      (node (ref "L2") (pin "2") (pinfunction "2_2") (pintype "passive"))
      (node (ref "U2") (pin "11") (pinfunction "VDD_PA_11") (pintype "power_in"))
    )
    (net (code "52") (name "Net-(U2-XC1)") (class "Default")
      (node (ref "C14") (pin "2") (pinfunction "2_2") (pintype "passive"))
      (node (ref "Q2") (pin "1") (pinfunction "1_1") (pintype "passive"))
      (node (ref "U2") (pin "10") (pinfunction "XC1_10") (pintype "input"))
    )
    (net (code "53") (name "Net-(U2-XC2)") (class "Default")
      (node (ref "C15") (pin "2") (pinfunction "2_2") (pintype "passive"))
      (node (ref "Q2") (pin "2") (pinfunction "2_2") (pintype "passive"))
      (node (ref "U2") (pin "9") (pinfunction "XC2_9") (pintype "output"))
    )
    (net (code "54") (name "RTS") (class "Default")
      (node (ref "CP2102") (pin "24") (pinfunction "RTS_24") (pintype "output"))
      (node (ref "R27") (pin "2") (pinfunction "2_2") (pintype "passive"))
      (node (ref "T3") (pin "E") (pinfunction "E_E") (pintype "passive"))
    )
    (net (code "55") (name "RXD") (class "Default")
      (node (ref "CP2102") (pin "25") (pinfunction "RXD_25") (pintype "input"))
      (node (ref "R29") (pin "1") (pinfunction "1_1") (pintype "passive"))
    )
    (net (code "56") (name "RXD0") (class "Default")
      (node (ref "R28") (pin "2") (pinfunction "2_2") (pintype "passive"))
      (node (ref "U5") (pin "34") (pinfunction "RXD0_34") (pintype "bidirectional"))
    )
    (net (code "57") (name "SENSOR_VN") (class "Default")
      (node (ref "U5") (pin "5") (pinfunction "SENSOR_VN_5") (pintype "input"))
    )
    (net (code "58") (name "SENSOR_VP") (class "Default")
      (node (ref "U5") (pin "4") (pinfunction "SENSOR_VP_4") (pintype "input"))
    )
    (net (code "59") (name "TXD") (class "Default")
      (node (ref "CP2102") (pin "26") (pinfunction "TXD_26") (pintype "output"))
      (node (ref "R28") (pin "1") (pinfunction "1_1") (pintype "passive"))
    )
    (net (code "60") (name "TXD0") (class "Default")
      (node (ref "R29") (pin "2") (pinfunction "2_2") (pintype "passive"))
      (node (ref "U5") (pin "35") (pinfunction "TXD0_35") (pintype "bidirectional"))
    )
    (net (code "61") (name "VBUS") (class "Default")
      (node (ref "C5") (pin "1") (pinfunction "1_1") (pintype "passive"))
      (node (ref "C6") (pin "1") (pinfunction "1_1") (pintype "passive"))
      (node (ref "CP2102") (pin "7") (pinfunction "REGIN_7") (pintype "passive"))
      (node (ref "CP2102") (pin "8") (pinfunction "VBUS_8") (pintype "input"))
      (node (ref "D2") (pin "A") (pinfunction "A_A") (pintype "passive"))
      (node (ref "FERRIT1") (pin "2") (pinfunction "2_2") (pintype "passive"))
      (node (ref "R3") (pin "2") (pinfunction "2_2") (pintype "passive"))
      (node (ref "R4") (pin "1") (pinfunction "1_1") (pintype "passive"))
    )
    (net (code "62") (name "unconnected-(CP2102-CTS-Pad23)") (class "Default")
      (node (ref "CP2102") (pin "23") (pinfunction "CTS_23") (pintype "input"))
    )
    (net (code "63") (name "unconnected-(CP2102-DCD-Pad1)") (class "Default")
      (node (ref "CP2102") (pin "1") (pinfunction "DCD_1") (pintype "input"))
    )
    (net (code "64") (name "unconnected-(CP2102-DSR-Pad27)") (class "Default")
      (node (ref "CP2102") (pin "27") (pinfunction "DSR_27") (pintype "input"))
    )
    (net (code "65") (name "unconnected-(CP2102-RI-Pad2)") (class "Default")
      (node (ref "CP2102") (pin "2") (pinfunction "RI_2") (pintype "input"))
    )
    (net (code "66") (name "unconnected-(CP2102-SUSPEND-Pad12)") (class "Default")
      (node (ref "CP2102") (pin "12") (pinfunction "SUSPEND_12") (pintype "output"))
    )
    (net (code "67") (name "unconnected-(CP2102-~{SUSPEND}-Pad11)") (class "Default")
      (node (ref "CP2102") (pin "11") (pinfunction "~{SUSPEND}_11") (pintype "output"))
    )
    (net (code "68") (name "unconnected-(MPU5060-AUX_CL-Pad7)") (class "Default")
      (node (ref "MPU5060") (pin "7") (pinfunction "AUX_CL_7") (pintype "input"))
    )
    (net (code "69") (name "unconnected-(MPU5060-AUX_DA-Pad6)") (class "Default")
      (node (ref "MPU5060") (pin "6") (pinfunction "AUX_DA_6") (pintype "bidirectional"))
    )
    (net (code "70") (name "unconnected-(MPU5060-RESV-Pad19)") (class "Default")
      (node (ref "MPU5060") (pin "19") (pinfunction "RESV_19") (pintype "passive"))
    )
    (net (code "71") (name "unconnected-(MPU5060-RESV-Pad21)") (class "Default")
      (node (ref "MPU5060") (pin "21") (pinfunction "RESV_21") (pintype "passive"))
    )
    (net (code "72") (name "unconnected-(MPU5060-RESV-Pad22)") (class "Default")
      (node (ref "MPU5060") (pin "22") (pinfunction "RESV_22") (pintype "passive"))
    )
    (net (code "73") (name "unconnected-(U5-SCK{slash}CLK-Pad20)") (class "Default")
      (node (ref "U5") (pin "20") (pinfunction "SCK/CLK_20") (pintype "bidirectional"))
    )
    (net (code "74") (name "unconnected-(U5-SCS{slash}CMD-Pad19)") (class "Default")
      (node (ref "U5") (pin "19") (pinfunction "SCS/CMD_19") (pintype "bidirectional"))
    )
    (net (code "75") (name "unconnected-(U5-SDI{slash}SD1-Pad22)") (class "Default")
      (node (ref "U5") (pin "22") (pinfunction "SDI/SD1_22") (pintype "bidirectional"))
    )
    (net (code "76") (name "unconnected-(U5-SDO{slash}SD0-Pad21)") (class "Default")
      (node (ref "U5") (pin "21") (pinfunction "SDO/SD0_21") (pintype "bidirectional"))
    )
    (net (code "77") (name "unconnected-(U5-SHD{slash}SD2-Pad17)") (class "Default")
      (node (ref "U5") (pin "17") (pinfunction "SHD/SD2_17") (pintype "bidirectional"))
    )
    (net (code "78") (name "unconnected-(U5-SWP{slash}SD3-Pad18)") (class "Default")
      (node (ref "U5") (pin "18") (pinfunction "SWP/SD3_18") (pintype "bidirectional"))
    )
    (net (code "79") (name "unconnected-(X2-Pad4)") (class "Default")
      (node (ref "X2") (pin "4") (pinfunction "4_4") (pintype "passive"))
    )
  )
)
